# 20223.net
KiCad netlist of a schematic drawn in EAGLE
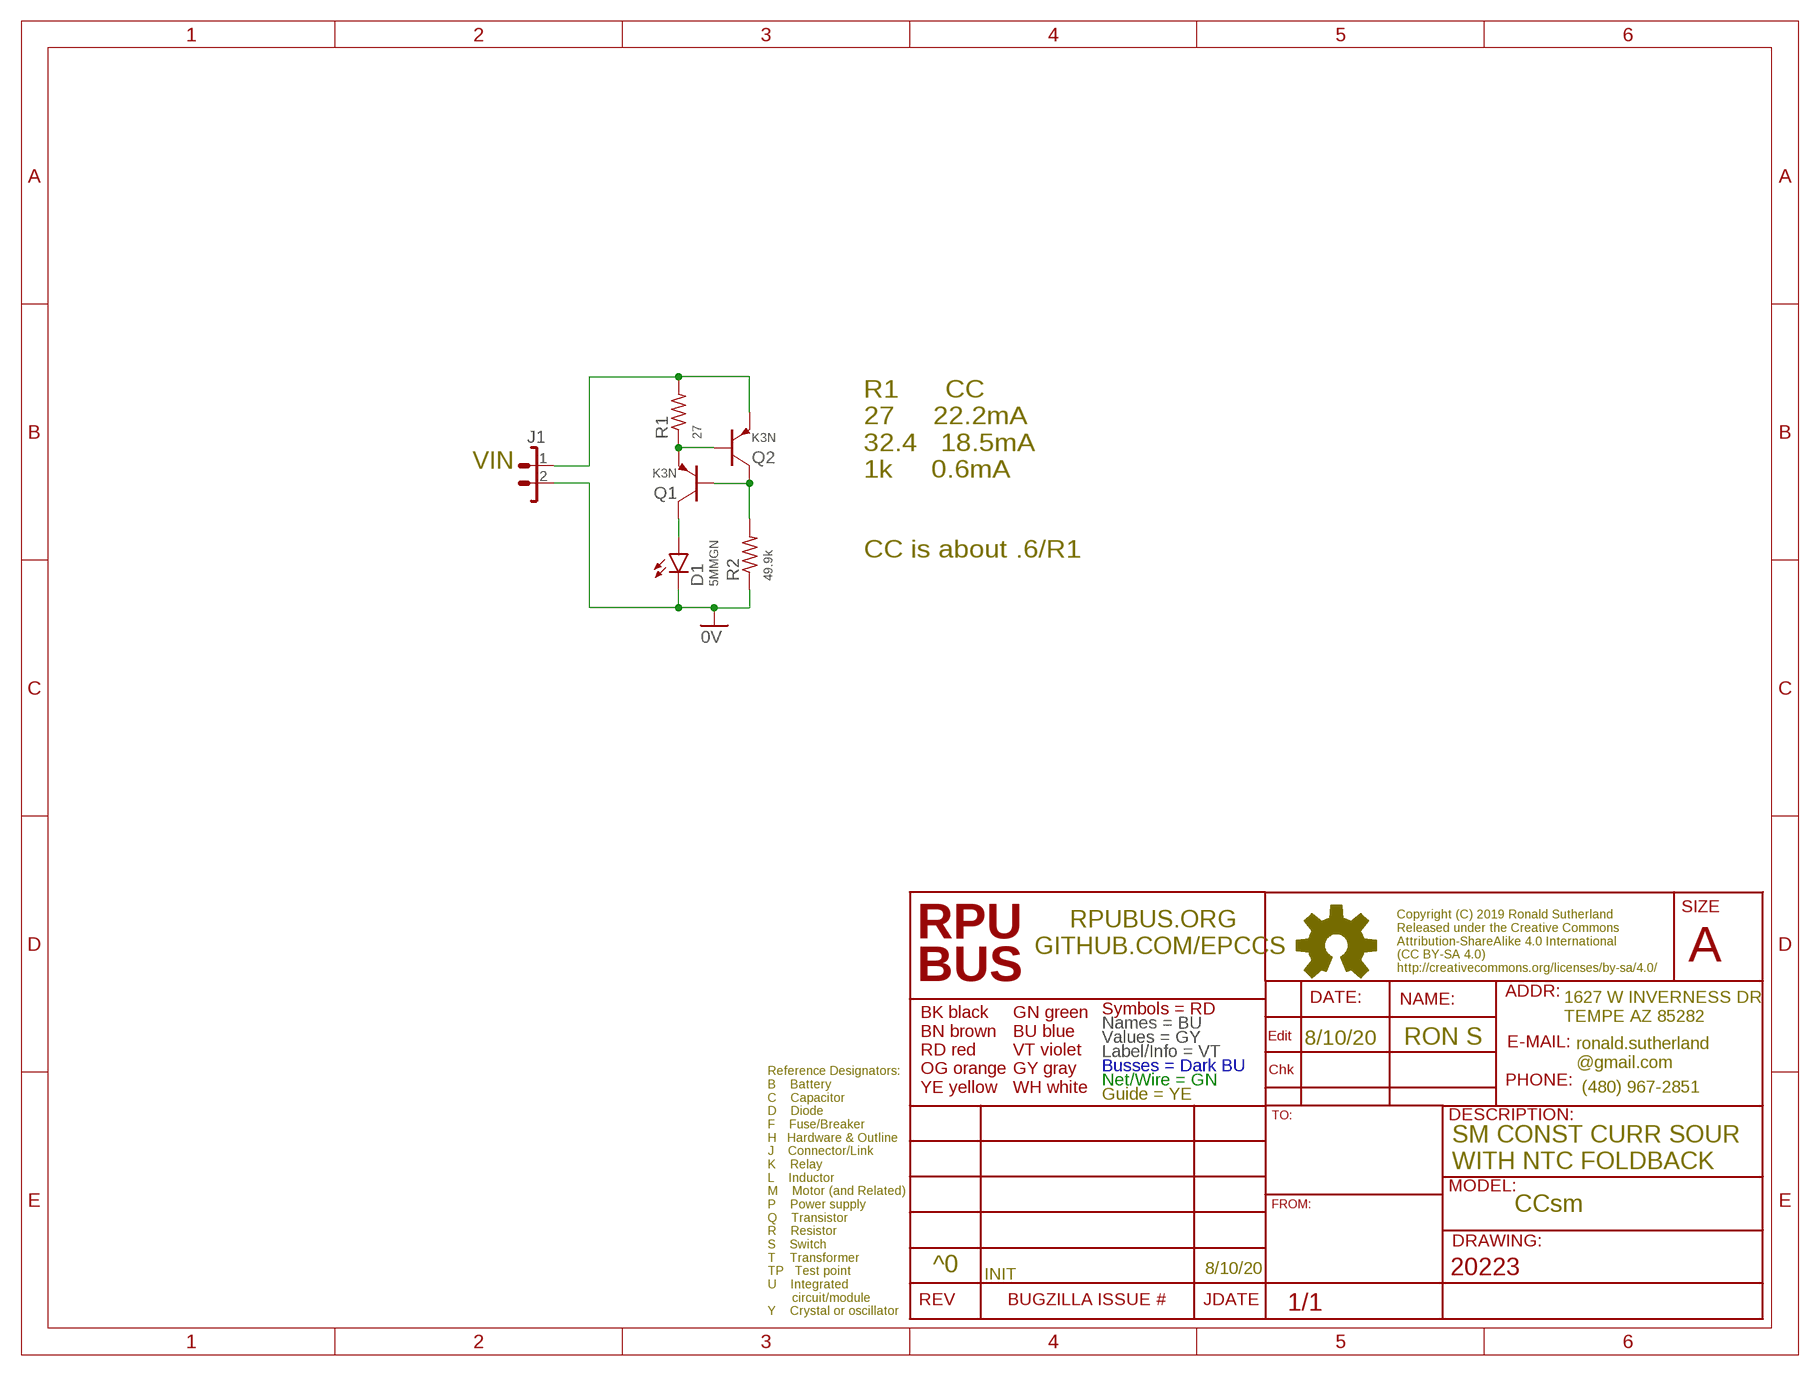
[diagram p0: schematic, sheet 1]

(export (version "E")
  (design (tool "Eeschema 10.0.6"))
  (components
    (comp (ref "D1")
      (value "5MMGN")
      (footprint "eagle-import:LED5MM")
      (libsource (lib "eagle-import") (part "LED5MM"))
    )
    (comp (ref "J1")
      (value "1X2")
      (footprint "eagle-import:1X2")
      (libsource (lib "eagle-import") (part "1X2"))
    )
    (comp (ref "Q1")
      (value "K3N")
      (footprint "eagle-import:SOT23")
      (libsource (lib "eagle-import") (part "PNPSOT23"))
    )
    (comp (ref "Q2")
      (value "K3N")
      (footprint "eagle-import:SOT23")
      (libsource (lib "eagle-import") (part "PNPSOT23"))
    )
    (comp (ref "R1")
      (value "27")
      (footprint "eagle-import:C0805(2012)")
      (libsource (lib "eagle-import") (part "R0805"))
    )
    (comp (ref "R2")
      (value "49.9k")
      (footprint "eagle-import:C0805(2012)")
      (libsource (lib "eagle-import") (part "R0805"))
    )
  )
  (nets
    (net (code "1") (name "0V") (class "Default")
      (node (ref "D1") (pin "K") (pinfunction "K_K") (pintype "passive"))
      (node (ref "J1") (pin "2") (pinfunction "2_2") (pintype "passive"))
      (node (ref "R2") (pin "1") (pinfunction "1_1") (pintype "passive"))
    )
    (net (code "2") (name "Net-(D1-PadA)") (class "Default")
      (node (ref "D1") (pin "A") (pinfunction "A_A") (pintype "passive"))
      (node (ref "Q1") (pin "C") (pinfunction "C_C") (pintype "passive"))
    )
    (net (code "3") (name "Net-(J1-Pad1)") (class "Default")
      (node (ref "J1") (pin "1") (pinfunction "1_1") (pintype "passive"))
      (node (ref "Q2") (pin "E") (pinfunction "E_E") (pintype "passive"))
      (node (ref "R1") (pin "2") (pinfunction "2_2") (pintype "passive"))
    )
    (net (code "4") (name "Net-(Q1-PadB)") (class "Default")
      (node (ref "Q1") (pin "B") (pinfunction "B_B") (pintype "passive"))
      (node (ref "Q2") (pin "C") (pinfunction "C_C") (pintype "passive"))
      (node (ref "R2") (pin "2") (pinfunction "2_2") (pintype "passive"))
    )
    (net (code "5") (name "Net-(Q1-PadE)") (class "Default")
      (node (ref "Q1") (pin "E") (pinfunction "E_E") (pintype "passive"))
      (node (ref "Q2") (pin "B") (pinfunction "B_B") (pintype "passive"))
      (node (ref "R1") (pin "1") (pinfunction "1_1") (pintype "passive"))
    )
  )
)
